# AT42QT1010_Capacitive_Touch_Breakout.net
KiCad netlist of a schematic drawn in EAGLE
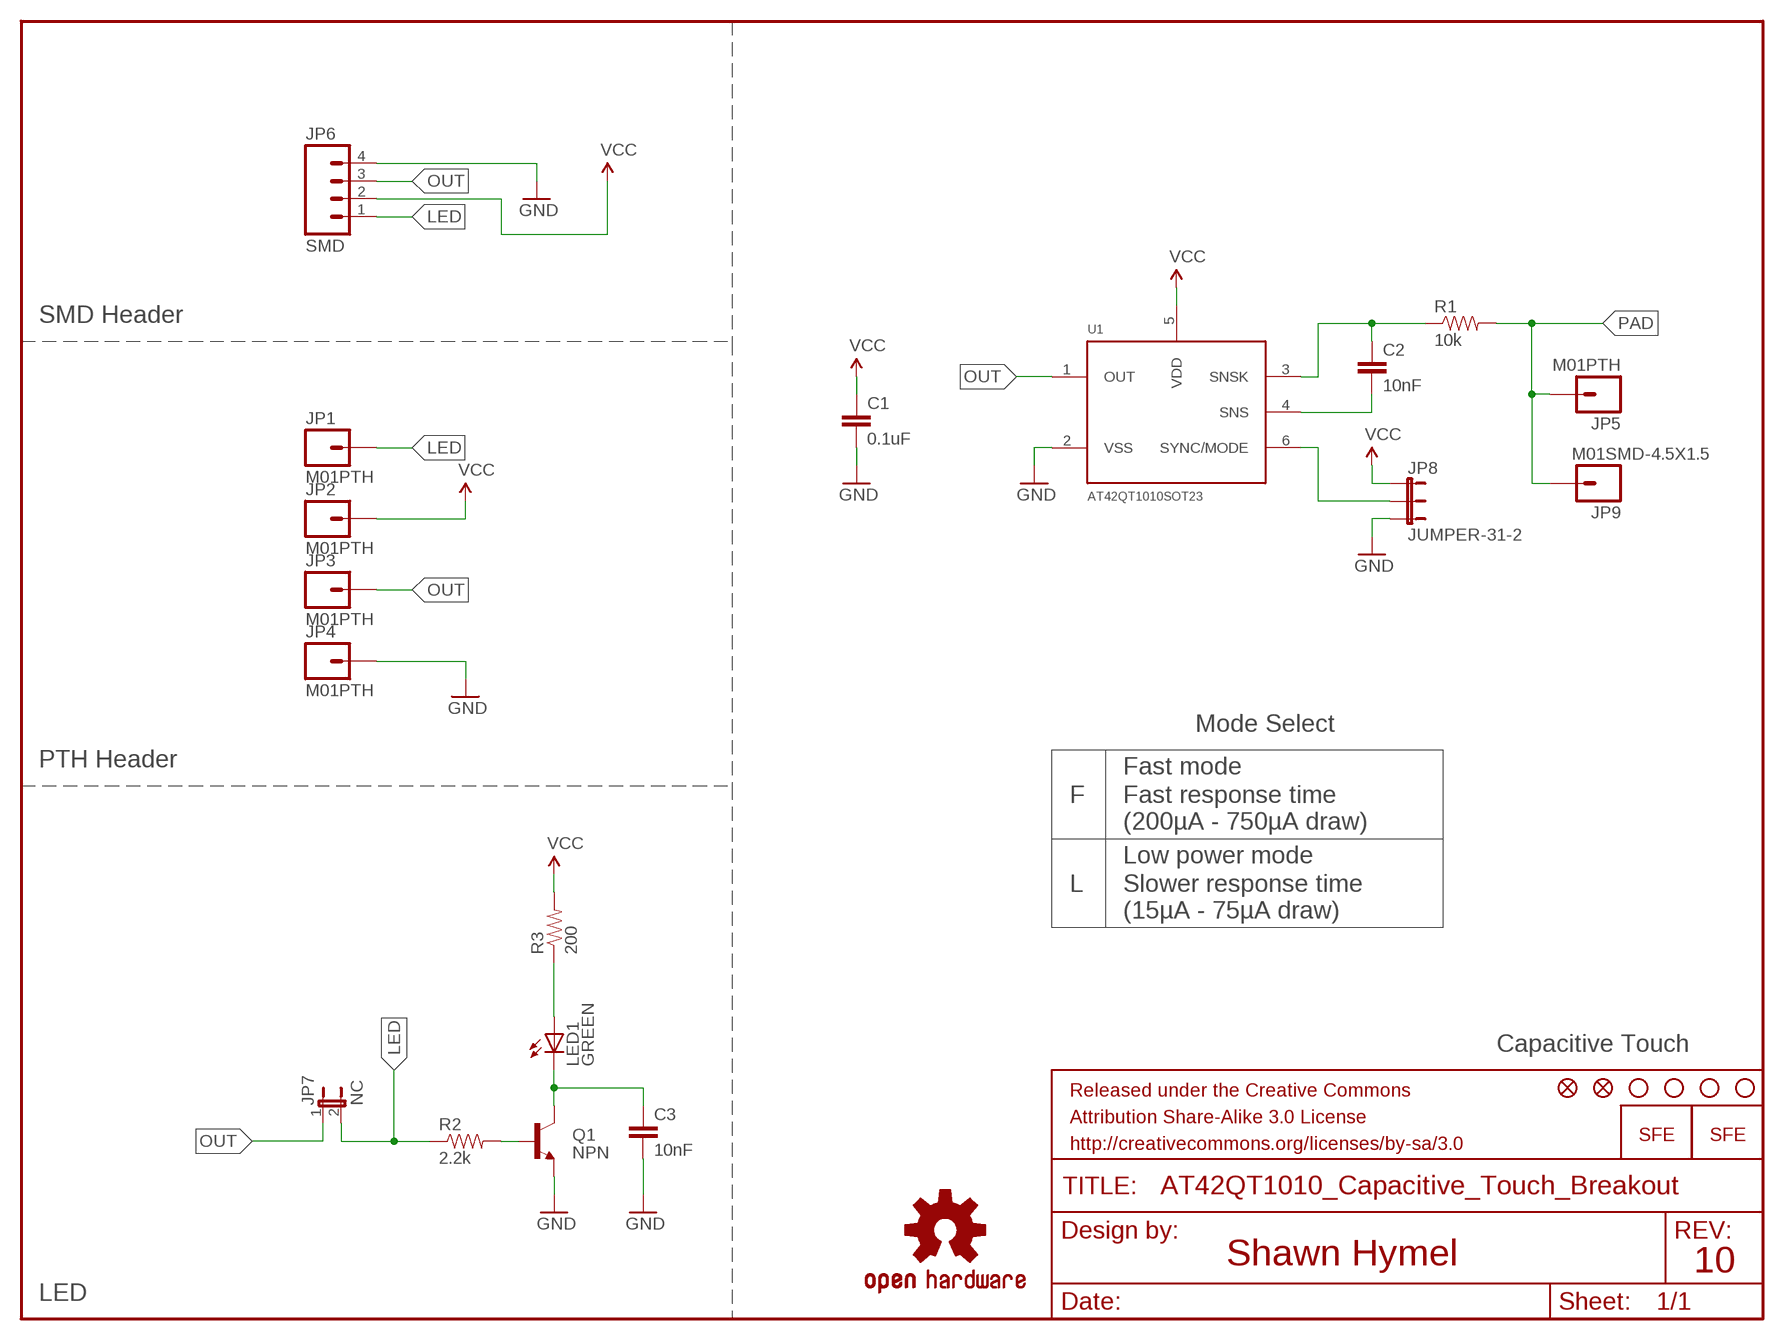
[diagram p0: schematic, sheet 1]

(export (version "E")
  (design (tool "Eeschema 10.0.6"))
  (components
    (comp (ref "C1")
      (value "0.1uF")
      (footprint "eagle-import:0603-CAP")
      (libsource (lib "eagle-import") (part "CAP0603-CAP"))
    )
    (comp (ref "C2")
      (value "10nF")
      (footprint "eagle-import:0603-CAP")
      (libsource (lib "eagle-import") (part "CAP0603-CAP"))
    )
    (comp (ref "C3")
      (value "10nF")
      (footprint "eagle-import:0603-CAP")
      (libsource (lib "eagle-import") (part "CAP0603-CAP"))
    )
    (comp (ref "FID1")
      (value "FIDUCIAL1X2")
      (footprint "eagle-import:FIDUCIAL-1X2")
      (libsource (lib "eagle-import") (part "FIDUCIAL1X2"))
    )
    (comp (ref "FID2")
      (value "FIDUCIAL1X2")
      (footprint "eagle-import:FIDUCIAL-1X2")
      (libsource (lib "eagle-import") (part "FIDUCIAL1X2"))
    )
    (comp (ref "FRAME1")
      (value "FRAME-LETTER")
      (footprint "eagle-import:CREATIVE_COMMONS")
      (libsource (lib "eagle-import") (part "FRAME-LETTER"))
    )
    (comp (ref "JP1")
      (value "M01PTH")
      (footprint "eagle-import:1X01")
      (libsource (lib "eagle-import") (part "M01PTH"))
    )
    (comp (ref "JP2")
      (value "M01PTH")
      (footprint "eagle-import:1X01")
      (libsource (lib "eagle-import") (part "M01PTH"))
    )
    (comp (ref "JP3")
      (value "M01PTH")
      (footprint "eagle-import:1X01")
      (libsource (lib "eagle-import") (part "M01PTH"))
    )
    (comp (ref "JP4")
      (value "M01PTH")
      (footprint "eagle-import:1X01")
      (libsource (lib "eagle-import") (part "M01PTH"))
    )
    (comp (ref "JP5")
      (value "M01PTH")
      (footprint "eagle-import:1X01")
      (libsource (lib "eagle-import") (part "M01PTH"))
    )
    (comp (ref "JP6")
      (value "SMD")
      (footprint "eagle-import:1X04-SMD_LONG")
      (libsource (lib "eagle-import") (part "M04SMD_LONG"))
    )
    (comp (ref "JP7")
      (value "NC")
      (footprint "eagle-import:SJ_2S")
      (libsource (lib "eagle-import") (part "JUMPER-2SMD-NC"))
    )
    (comp (ref "JP8")
      (value "JUMPER-31-2")
      (footprint "eagle-import:SJ_3_PASTE1&2")
      (libsource (lib "eagle-import") (part "JUMPER-31-2"))
    )
    (comp (ref "JP9")
      (value "M01SMD-4.5X1.5")
      (footprint "eagle-import:PAD-1.5X4.5")
      (libsource (lib "eagle-import") (part "M01SMD-4.5X1.5"))
    )
    (comp (ref "LED1")
      (value "GREEN")
      (footprint "eagle-import:LED-1206-BOTTOM")
      (libsource (lib "eagle-import") (part "LED1206-BOTTOM"))
    )
    (comp (ref "LOGO1")
      (value "LOGO-SFENEW")
      (footprint "eagle-import:SFE-NEW-WEBLOGO")
      (libsource (lib "eagle-import") (part "LOGO-SFENEW"))
    )
    (comp (ref "LOGO2")
      (value "OSHW-LOGOS")
      (footprint "eagle-import:OSHW-LOGO-S")
      (libsource (lib "eagle-import") (part "OSHW-LOGOS"))
    )
    (comp (ref "LOGO3")
      (value "LOGO-SFESK")
      (footprint "eagle-import:SFE-LOGO-FLAME")
      (libsource (lib "eagle-import") (part "LOGO-SFESK"))
    )
    (comp (ref "Q1")
      (value "NPN")
      (footprint "eagle-import:SOT23")
      (libsource (lib "eagle-import") (part "TRANSISTOR_NPNMMBT2222A"))
    )
    (comp (ref "R1")
      (value "10k")
      (footprint "eagle-import:0603-RES")
      (libsource (lib "eagle-import") (part "RESISTOR0603"))
    )
    (comp (ref "R2")
      (value "2.2k")
      (footprint "eagle-import:0603-RES")
      (libsource (lib "eagle-import") (part "RESISTOR0603"))
    )
    (comp (ref "R3")
      (value "200")
      (footprint "eagle-import:0603-RES")
      (libsource (lib "eagle-import") (part "RESISTOR0603"))
    )
    (comp (ref "STANDOFF1")
      (value "STAND-OFF")
      (footprint "eagle-import:STAND-OFF")
      (libsource (lib "eagle-import") (part "STAND-OFF"))
    )
    (comp (ref "STANDOFF2")
      (value "STAND-OFF")
      (footprint "eagle-import:STAND-OFF")
      (libsource (lib "eagle-import") (part "STAND-OFF"))
    )
    (comp (ref "STANDOFF3")
      (value "STAND-OFF")
      (footprint "eagle-import:STAND-OFF")
      (libsource (lib "eagle-import") (part "STAND-OFF"))
    )
    (comp (ref "STANDOFF4")
      (value "STAND-OFF")
      (footprint "eagle-import:STAND-OFF")
      (libsource (lib "eagle-import") (part "STAND-OFF"))
    )
    (comp (ref "U1")
      (value "AT42QT1010SOT23")
      (footprint "eagle-import:SOT23-6")
      (libsource (lib "eagle-import") (part "AT42QT1010SOT23"))
    )
  )
  (nets
    (net (code "1") (name "GND") (class "Default")
      (node (ref "C1") (pin "2") (pinfunction "2_2") (pintype "passive"))
      (node (ref "C3") (pin "2") (pinfunction "2_2") (pintype "passive"))
      (node (ref "JP4") (pin "1") (pinfunction "1_1") (pintype "passive"))
      (node (ref "JP6") (pin "4") (pinfunction "4_4") (pintype "passive"))
      (node (ref "JP8") (pin "3") (pinfunction "3_3") (pintype "passive"))
      (node (ref "Q1") (pin "2") (pinfunction "E_2") (pintype "passive"))
      (node (ref "U1") (pin "2") (pinfunction "VSS_2") (pintype "bidirectional"))
    )
    (net (code "2") (name "LED") (class "Default")
      (node (ref "JP1") (pin "1") (pinfunction "1_1") (pintype "passive"))
      (node (ref "JP6") (pin "1") (pinfunction "1_1") (pintype "passive"))
      (node (ref "JP7") (pin "2") (pinfunction "2_2") (pintype "passive"))
      (node (ref "R2") (pin "1") (pinfunction "1_1") (pintype "passive"))
    )
    (net (code "3") (name "Net-(LED1-PadA)") (class "Default")
      (node (ref "LED1") (pin "A") (pinfunction "A_A") (pintype "passive"))
      (node (ref "R3") (pin "1") (pinfunction "1_1") (pintype "passive"))
    )
    (net (code "4") (name "Net-(Q1-B)") (class "Default")
      (node (ref "Q1") (pin "1") (pinfunction "B_1") (pintype "passive"))
      (node (ref "R2") (pin "2") (pinfunction "2_2") (pintype "passive"))
    )
    (net (code "5") (name "Net-(Q1-C)") (class "Default")
      (node (ref "C3") (pin "1") (pinfunction "1_1") (pintype "passive"))
      (node (ref "LED1") (pin "C") (pinfunction "C_C") (pintype "passive"))
      (node (ref "Q1") (pin "3") (pinfunction "C_3") (pintype "passive"))
    )
    (net (code "6") (name "Net-(U1-SNS)") (class "Default")
      (node (ref "C2") (pin "2") (pinfunction "2_2") (pintype "passive"))
      (node (ref "U1") (pin "4") (pinfunction "SNS_4") (pintype "bidirectional"))
    )
    (net (code "7") (name "Net-(U1-SNSK)") (class "Default")
      (node (ref "C2") (pin "1") (pinfunction "1_1") (pintype "passive"))
      (node (ref "R1") (pin "1") (pinfunction "1_1") (pintype "passive"))
      (node (ref "U1") (pin "3") (pinfunction "SNSK_3") (pintype "bidirectional"))
    )
    (net (code "8") (name "Net-(U1-SYNC{slash}MODE)") (class "Default")
      (node (ref "JP8") (pin "2") (pinfunction "2_2") (pintype "passive"))
      (node (ref "U1") (pin "6") (pinfunction "SYNC/MODE_6") (pintype "bidirectional"))
    )
    (net (code "9") (name "OUT") (class "Default")
      (node (ref "JP3") (pin "1") (pinfunction "1_1") (pintype "passive"))
      (node (ref "JP6") (pin "3") (pinfunction "3_3") (pintype "passive"))
      (node (ref "JP7") (pin "1") (pinfunction "1_1") (pintype "passive"))
      (node (ref "U1") (pin "1") (pinfunction "OUT_1") (pintype "bidirectional"))
    )
    (net (code "10") (name "PAD") (class "Default")
      (node (ref "JP5") (pin "1") (pinfunction "1_1") (pintype "passive"))
      (node (ref "JP9") (pin "P$1") (pinfunction "1_P$1") (pintype "passive"))
      (node (ref "R1") (pin "2") (pinfunction "2_2") (pintype "passive"))
    )
    (net (code "11") (name "VCC") (class "Default")
      (node (ref "C1") (pin "1") (pinfunction "1_1") (pintype "passive"))
      (node (ref "JP2") (pin "1") (pinfunction "1_1") (pintype "passive"))
      (node (ref "JP6") (pin "2") (pinfunction "2_2") (pintype "passive"))
      (node (ref "JP8") (pin "1") (pinfunction "1_1") (pintype "passive"))
      (node (ref "R3") (pin "2") (pinfunction "2_2") (pintype "passive"))
      (node (ref "U1") (pin "5") (pinfunction "VDD_5") (pintype "bidirectional"))
    )
  )
)
